# HackCube_2.net
KiCad netlist of a schematic drawn in Altium Designer
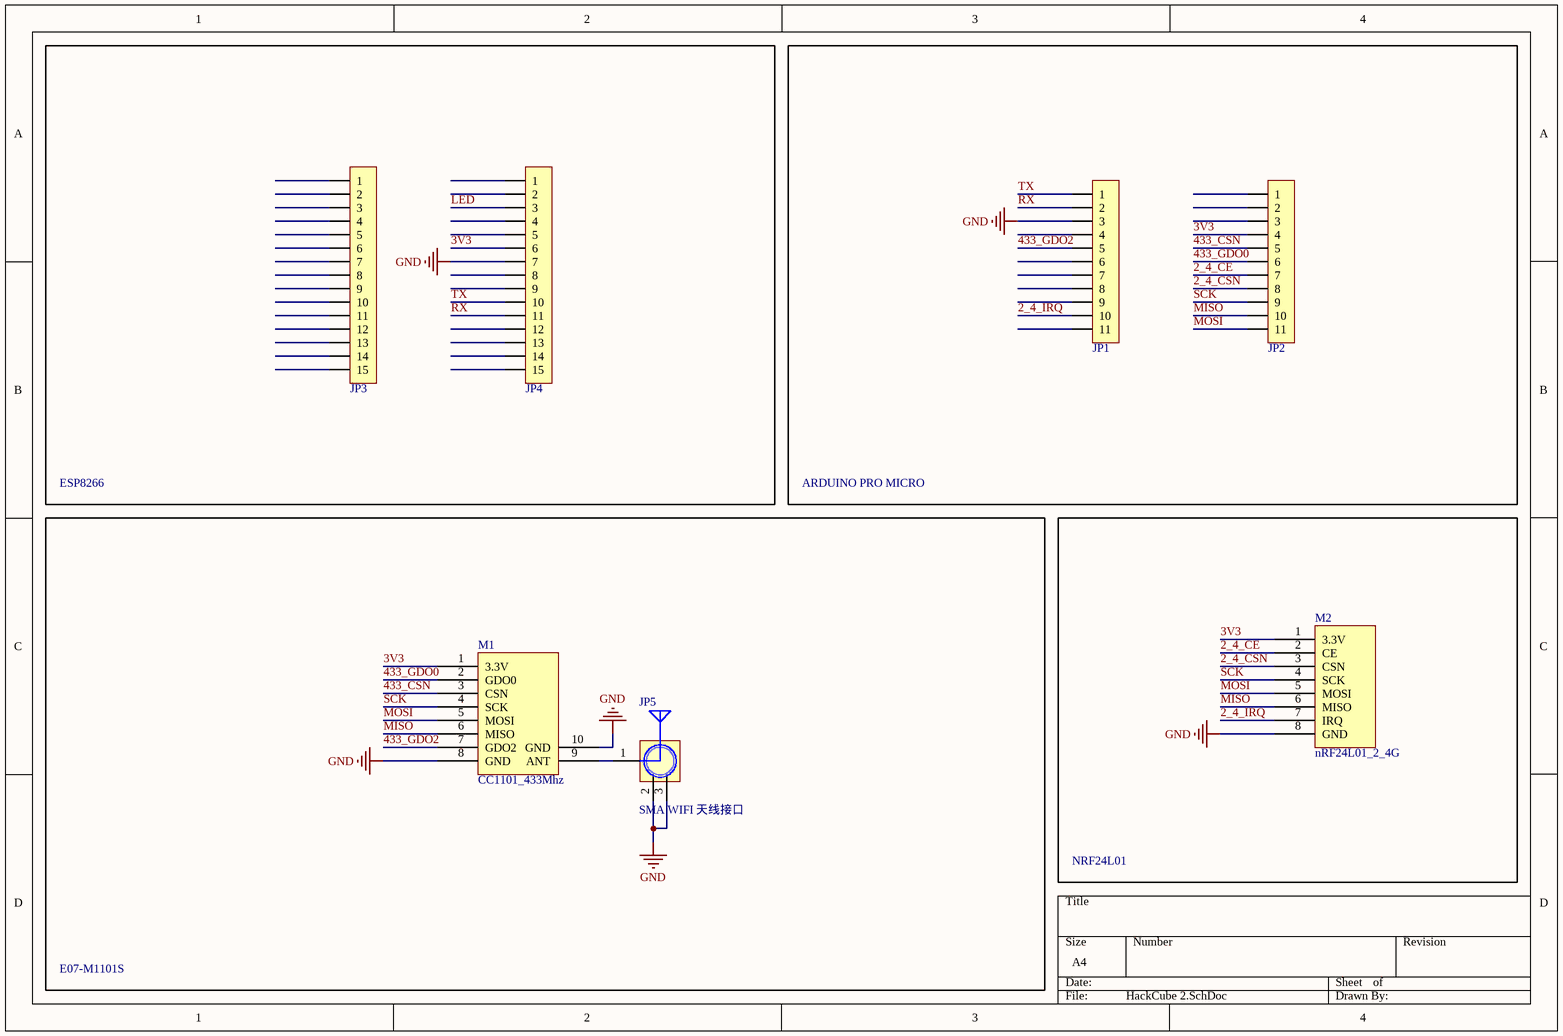
[diagram p0: HackCube 2.SchDoc]

(export (version "E")
  (design (tool "Eeschema 10.0.6"))
  (components
    (comp (ref "JP1")
      (value "HDR-1X11")
      (footprint "HDR2.54-LI-11P")
      (description "11P接插件")
      (fields (field (name "版权归属") "源创客"))
      (libsource (lib "4.6   - 接插件-脚距2.54") (part "Header 11"))
    )
    (comp (ref "JP2")
      (value "HDR-1X11")
      (footprint "HDR2.54-LI-11P")
      (description "11P接插件")
      (fields (field (name "版权归属") "源创客"))
      (libsource (lib "4.6   - 接插件-脚距2.54") (part "Header 11"))
    )
    (comp (ref "JP3")
      (value "HDR-1X15")
      (footprint "HDR2.54-LI-15P")
      (description "15P接插件")
      (fields (field (name "版权归属") "源创客"))
      (libsource (lib "4.6   - 接插件-脚距2.54") (part "Header 15"))
    )
    (comp (ref "JP4")
      (value "HDR-1X15")
      (footprint "HDR2.54-LI-15P")
      (description "15P接插件")
      (fields (field (name "版权归属") "源创客"))
      (libsource (lib "4.6   - 接插件-脚距2.54") (part "Header 15"))
    )
    (comp (ref "JP5")
      (value "SMA WIFI 天线接口")
      (footprint "SMA-KE")
      (description "SMA-2.4G射频天线接口")
      (fields (field (name "版权归属") "源创客"))
      (libsource (lib "14.1 - 天线") (part "SMA"))
    )
    (comp (ref "M1")
      (value "CC1101_433Mhz")
      (footprint "PE07-M1101S")
      (libsource (lib "13.1 - 模块") (part "CC1101_433Mhz"))
    )
    (comp (ref "M2")
      (value "nRF24L01_2_4G")
      (footprint "PE01-ML01SP2")
      (libsource (lib "13.1 - 模块") (part "nRF24L01_2_4G"))
    )
  )
  (nets
    (net (code "1") (name "/2_4_CE") (class "Default")
      (node (ref "JP2") (pin "7") (pinfunction "7_7") (pintype "passive"))
      (node (ref "M2") (pin "2") (pinfunction "CE_2") (pintype "passive"))
    )
    (net (code "2") (name "/2_4_CSN") (class "Default")
      (node (ref "JP2") (pin "8") (pinfunction "8_8") (pintype "passive"))
      (node (ref "M2") (pin "3") (pinfunction "CSN_3") (pintype "passive"))
    )
    (net (code "3") (name "/2_4_IRQ") (class "Default")
      (node (ref "JP1") (pin "10") (pinfunction "10_10") (pintype "passive"))
      (node (ref "M2") (pin "7") (pinfunction "IRQ_7") (pintype "passive"))
    )
    (net (code "4") (name "/3V3") (class "Default")
      (node (ref "JP2") (pin "4") (pinfunction "4_4") (pintype "passive"))
      (node (ref "JP4") (pin "6") (pinfunction "6_6") (pintype "passive"))
      (node (ref "M1") (pin "1") (pinfunction "3.3V_1") (pintype "passive"))
      (node (ref "M2") (pin "1") (pinfunction "3.3V_1") (pintype "passive"))
    )
    (net (code "5") (name "/433_CSN") (class "Default")
      (node (ref "JP2") (pin "5") (pinfunction "5_5") (pintype "passive"))
      (node (ref "M1") (pin "3") (pinfunction "CSN_3") (pintype "passive"))
    )
    (net (code "6") (name "/433_GDO0") (class "Default")
      (node (ref "JP2") (pin "6") (pinfunction "6_6") (pintype "passive"))
      (node (ref "M1") (pin "2") (pinfunction "GDO0_2") (pintype "passive"))
    )
    (net (code "7") (name "/433_GDO2") (class "Default")
      (node (ref "JP1") (pin "5") (pinfunction "5_5") (pintype "passive"))
      (node (ref "M1") (pin "7") (pinfunction "GDO2_7") (pintype "passive"))
    )
    (net (code "8") (name "/LED") (class "Default")
      (node (ref "JP4") (pin "3") (pinfunction "3_3") (pintype "passive"))
    )
    (net (code "9") (name "/MISO") (class "Default")
      (node (ref "JP2") (pin "10") (pinfunction "10_10") (pintype "passive"))
      (node (ref "M1") (pin "6") (pinfunction "MISO_6") (pintype "passive"))
      (node (ref "M2") (pin "6") (pinfunction "MISO_6") (pintype "passive"))
    )
    (net (code "10") (name "/MOSI") (class "Default")
      (node (ref "JP2") (pin "11") (pinfunction "11_11") (pintype "passive"))
      (node (ref "M1") (pin "5") (pinfunction "MOSI_5") (pintype "passive"))
      (node (ref "M2") (pin "5") (pinfunction "MOSI_5") (pintype "passive"))
    )
    (net (code "11") (name "/RX") (class "Default")
      (node (ref "JP1") (pin "2") (pinfunction "2_2") (pintype "passive"))
      (node (ref "JP4") (pin "11") (pinfunction "11_11") (pintype "passive"))
    )
    (net (code "12") (name "/SCK") (class "Default")
      (node (ref "JP2") (pin "9") (pinfunction "9_9") (pintype "passive"))
      (node (ref "M1") (pin "4") (pinfunction "SCK_4") (pintype "passive"))
      (node (ref "M2") (pin "4") (pinfunction "SCK_4") (pintype "passive"))
    )
    (net (code "13") (name "/TX") (class "Default")
      (node (ref "JP1") (pin "1") (pinfunction "1_1") (pintype "passive"))
      (node (ref "JP4") (pin "10") (pinfunction "10_10") (pintype "passive"))
    )
    (net (code "14") (name "GND") (class "Default")
      (node (ref "JP1") (pin "3") (pinfunction "3_3") (pintype "passive"))
      (node (ref "JP4") (pin "7") (pinfunction "7_7") (pintype "passive"))
      (node (ref "JP5") (pin "2") (pinfunction "GND_2") (pintype "passive"))
      (node (ref "JP5") (pin "3") (pinfunction "GND_3") (pintype "passive"))
      (node (ref "M1") (pin "10") (pinfunction "GND_10") (pintype "passive"))
      (node (ref "M1") (pin "8") (pinfunction "GND_8") (pintype "passive"))
      (node (ref "M2") (pin "8") (pinfunction "GND_8") (pintype "passive"))
    )
    (net (code "15") (name "Net-(JP5-ANT)") (class "Default")
      (node (ref "JP5") (pin "1") (pinfunction "ANT_1") (pintype "passive"))
      (node (ref "M1") (pin "9") (pinfunction "ANT_9") (pintype "passive"))
    )
    (net (code "16") (name "unconnected-(JP1-Pad4)") (class "Default")
      (node (ref "JP1") (pin "4") (pinfunction "4_4") (pintype "passive"))
    )
    (net (code "17") (name "unconnected-(JP1-Pad6)") (class "Default")
      (node (ref "JP1") (pin "6") (pinfunction "6_6") (pintype "passive"))
    )
    (net (code "18") (name "unconnected-(JP1-Pad7)") (class "Default")
      (node (ref "JP1") (pin "7") (pinfunction "7_7") (pintype "passive"))
    )
    (net (code "19") (name "unconnected-(JP1-Pad8)") (class "Default")
      (node (ref "JP1") (pin "8") (pinfunction "8_8") (pintype "passive"))
    )
    (net (code "20") (name "unconnected-(JP1-Pad9)") (class "Default")
      (node (ref "JP1") (pin "9") (pinfunction "9_9") (pintype "passive"))
    )
    (net (code "21") (name "unconnected-(JP1-Pad11)") (class "Default")
      (node (ref "JP1") (pin "11") (pinfunction "11_11") (pintype "passive"))
    )
    (net (code "22") (name "unconnected-(JP2-Pad1)") (class "Default")
      (node (ref "JP2") (pin "1") (pinfunction "1_1") (pintype "passive"))
    )
    (net (code "23") (name "unconnected-(JP2-Pad2)") (class "Default")
      (node (ref "JP2") (pin "2") (pinfunction "2_2") (pintype "passive"))
    )
    (net (code "24") (name "unconnected-(JP2-Pad3)") (class "Default")
      (node (ref "JP2") (pin "3") (pinfunction "3_3") (pintype "passive"))
    )
    (net (code "25") (name "unconnected-(JP3-Pad1)") (class "Default")
      (node (ref "JP3") (pin "1") (pinfunction "1_1") (pintype "passive"))
    )
    (net (code "26") (name "unconnected-(JP3-Pad2)") (class "Default")
      (node (ref "JP3") (pin "2") (pinfunction "2_2") (pintype "passive"))
    )
    (net (code "27") (name "unconnected-(JP3-Pad3)") (class "Default")
      (node (ref "JP3") (pin "3") (pinfunction "3_3") (pintype "passive"))
    )
    (net (code "28") (name "unconnected-(JP3-Pad4)") (class "Default")
      (node (ref "JP3") (pin "4") (pinfunction "4_4") (pintype "passive"))
    )
    (net (code "29") (name "unconnected-(JP3-Pad5)") (class "Default")
      (node (ref "JP3") (pin "5") (pinfunction "5_5") (pintype "passive"))
    )
    (net (code "30") (name "unconnected-(JP3-Pad6)") (class "Default")
      (node (ref "JP3") (pin "6") (pinfunction "6_6") (pintype "passive"))
    )
    (net (code "31") (name "unconnected-(JP3-Pad7)") (class "Default")
      (node (ref "JP3") (pin "7") (pinfunction "7_7") (pintype "passive"))
    )
    (net (code "32") (name "unconnected-(JP3-Pad8)") (class "Default")
      (node (ref "JP3") (pin "8") (pinfunction "8_8") (pintype "passive"))
    )
    (net (code "33") (name "unconnected-(JP3-Pad9)") (class "Default")
      (node (ref "JP3") (pin "9") (pinfunction "9_9") (pintype "passive"))
    )
    (net (code "34") (name "unconnected-(JP3-Pad10)") (class "Default")
      (node (ref "JP3") (pin "10") (pinfunction "10_10") (pintype "passive"))
    )
    (net (code "35") (name "unconnected-(JP3-Pad11)") (class "Default")
      (node (ref "JP3") (pin "11") (pinfunction "11_11") (pintype "passive"))
    )
    (net (code "36") (name "unconnected-(JP3-Pad12)") (class "Default")
      (node (ref "JP3") (pin "12") (pinfunction "12_12") (pintype "passive"))
    )
    (net (code "37") (name "unconnected-(JP3-Pad13)") (class "Default")
      (node (ref "JP3") (pin "13") (pinfunction "13_13") (pintype "passive"))
    )
    (net (code "38") (name "unconnected-(JP3-Pad14)") (class "Default")
      (node (ref "JP3") (pin "14") (pinfunction "14_14") (pintype "passive"))
    )
    (net (code "39") (name "unconnected-(JP3-Pad15)") (class "Default")
      (node (ref "JP3") (pin "15") (pinfunction "15_15") (pintype "passive"))
    )
    (net (code "40") (name "unconnected-(JP4-Pad1)") (class "Default")
      (node (ref "JP4") (pin "1") (pinfunction "1_1") (pintype "passive"))
    )
    (net (code "41") (name "unconnected-(JP4-Pad2)") (class "Default")
      (node (ref "JP4") (pin "2") (pinfunction "2_2") (pintype "passive"))
    )
    (net (code "42") (name "unconnected-(JP4-Pad4)") (class "Default")
      (node (ref "JP4") (pin "4") (pinfunction "4_4") (pintype "passive"))
    )
    (net (code "43") (name "unconnected-(JP4-Pad5)") (class "Default")
      (node (ref "JP4") (pin "5") (pinfunction "5_5") (pintype "passive"))
    )
    (net (code "44") (name "unconnected-(JP4-Pad8)") (class "Default")
      (node (ref "JP4") (pin "8") (pinfunction "8_8") (pintype "passive"))
    )
    (net (code "45") (name "unconnected-(JP4-Pad9)") (class "Default")
      (node (ref "JP4") (pin "9") (pinfunction "9_9") (pintype "passive"))
    )
    (net (code "46") (name "unconnected-(JP4-Pad12)") (class "Default")
      (node (ref "JP4") (pin "12") (pinfunction "12_12") (pintype "passive"))
    )
    (net (code "47") (name "unconnected-(JP4-Pad13)") (class "Default")
      (node (ref "JP4") (pin "13") (pinfunction "13_13") (pintype "passive"))
    )
    (net (code "48") (name "unconnected-(JP4-Pad14)") (class "Default")
      (node (ref "JP4") (pin "14") (pinfunction "14_14") (pintype "passive"))
    )
    (net (code "49") (name "unconnected-(JP4-Pad15)") (class "Default")
      (node (ref "JP4") (pin "15") (pinfunction "15_15") (pintype "passive"))
    )
  )
)
